# Main.net
KiCad netlist of a schematic drawn in Altium Designer
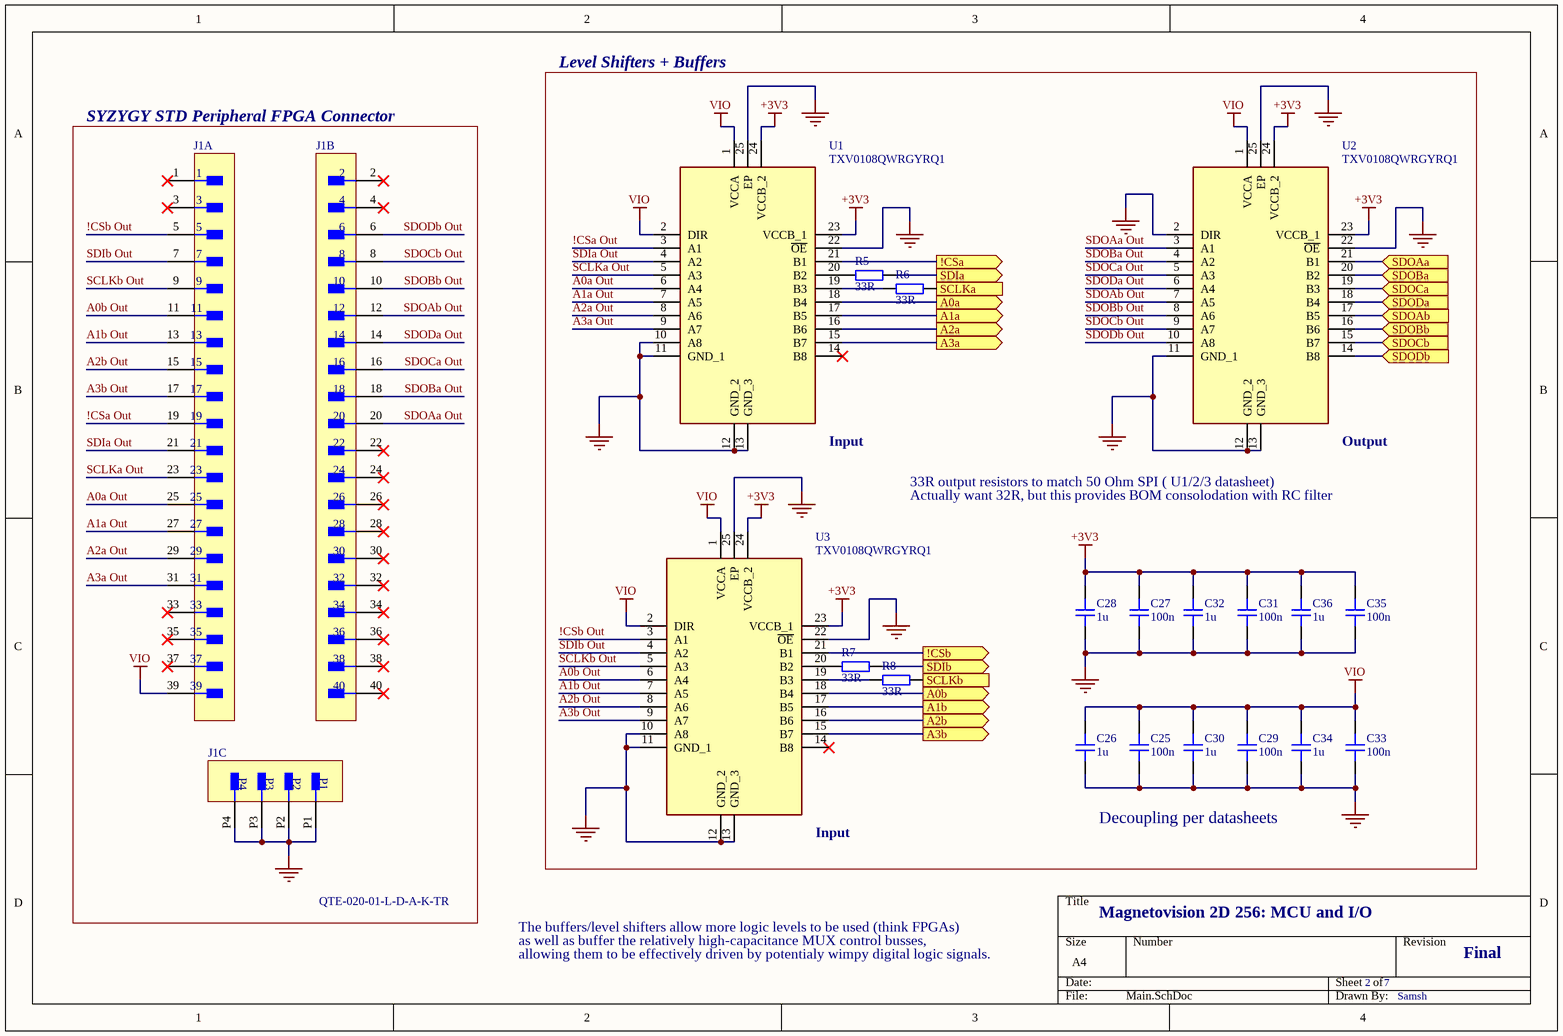
[diagram p0: Main.SchDoc]

(export (version "E")
  (design (tool "Eeschema 10.0.6"))
  (components
    (comp (ref "C25")
      (value "100n")
      (footprint "CAP_0603")
      (description "Capacitor SMD 0603")
      (fields (field (name "SOURCE") "Schematic-Lib-PhilsLab.SchLib"))
      (libsource (lib "Samsh Nanoelectronics") (part "CAP_EL_NP_5MM"))
    )
    (comp (ref "C26")
      (value "1u")
      (footprint "CAP_0603")
      (description "Capacitor SMD 0603")
      (fields (field (name "SOURCE") "Schematic-Lib-PhilsLab.SchLib"))
      (libsource (lib "Samsh Nanoelectronics") (part "CAP_EL_NP_5MM"))
    )
    (comp (ref "C27")
      (value "100n")
      (footprint "CAP_0603")
      (description "Capacitor SMD 0603")
      (fields (field (name "SOURCE") "Schematic-Lib-PhilsLab.SchLib"))
      (libsource (lib "Samsh Nanoelectronics") (part "CAP_EL_NP_5MM"))
    )
    (comp (ref "C28")
      (value "1u")
      (footprint "CAP_0603")
      (description "Capacitor SMD 0603")
      (fields (field (name "SOURCE") "Schematic-Lib-PhilsLab.SchLib"))
      (libsource (lib "Samsh Nanoelectronics") (part "CAP_EL_NP_5MM"))
    )
    (comp (ref "C29")
      (value "100n")
      (footprint "CAP_0603")
      (description "Capacitor SMD 0603")
      (fields (field (name "SOURCE") "Schematic-Lib-PhilsLab.SchLib"))
      (libsource (lib "Samsh Nanoelectronics") (part "CAP_EL_NP_5MM"))
    )
    (comp (ref "C30")
      (value "1u")
      (footprint "CAP_0603")
      (description "Capacitor SMD 0603")
      (fields (field (name "SOURCE") "Schematic-Lib-PhilsLab.SchLib"))
      (libsource (lib "Samsh Nanoelectronics") (part "CAP_EL_NP_5MM"))
    )
    (comp (ref "C31")
      (value "100n")
      (footprint "CAP_0603")
      (description "Capacitor SMD 0603")
      (fields (field (name "SOURCE") "Schematic-Lib-PhilsLab.SchLib"))
      (libsource (lib "Samsh Nanoelectronics") (part "CAP_EL_NP_5MM"))
    )
    (comp (ref "C32")
      (value "1u")
      (footprint "CAP_0603")
      (description "Capacitor SMD 0603")
      (fields (field (name "SOURCE") "Schematic-Lib-PhilsLab.SchLib"))
      (libsource (lib "Samsh Nanoelectronics") (part "CAP_EL_NP_5MM"))
    )
    (comp (ref "C33")
      (value "100n")
      (footprint "CAP_0603")
      (description "Capacitor SMD 0603")
      (fields (field (name "SOURCE") "Schematic-Lib-PhilsLab.SchLib"))
      (libsource (lib "Samsh Nanoelectronics") (part "CAP_EL_NP_5MM"))
    )
    (comp (ref "C34")
      (value "1u")
      (footprint "CAP_0603")
      (description "Capacitor SMD 0603")
      (fields (field (name "SOURCE") "Schematic-Lib-PhilsLab.SchLib"))
      (libsource (lib "Samsh Nanoelectronics") (part "CAP_EL_NP_5MM"))
    )
    (comp (ref "C35")
      (value "100n")
      (footprint "CAP_0603")
      (description "Capacitor SMD 0603")
      (fields (field (name "SOURCE") "Schematic-Lib-PhilsLab.SchLib"))
      (libsource (lib "Samsh Nanoelectronics") (part "CAP_EL_NP_5MM"))
    )
    (comp (ref "C36")
      (value "1u")
      (footprint "CAP_0603")
      (description "Capacitor SMD 0603")
      (fields (field (name "SOURCE") "Schematic-Lib-PhilsLab.SchLib"))
      (libsource (lib "Samsh Nanoelectronics") (part "CAP_EL_NP_5MM"))
    )
    (comp (ref "J1")
      (value "QTE-020-01-L-D-A-K-TR")
      (footprint "FP-QTE-020-01-L-D-A-K-TR_MFG")
      (description "Board to Board & Mezzanine Connectors Q Strip High-Speed Ground Plane Header, 0.80mm Pitch")
      (libsource (lib "") (part "95d99cab9a8bca80e36bdc8dd55fd41_1"))
    )
    (comp (ref "R5")
      (value "33R")
      (footprint "RES_0603")
      (description "Resistor SMD 0603")
      (fields (field (name "SOURCE") "Schematic-Lib-PhilsLab.SchLib"))
      (libsource (lib "Samsh Nanoelectronics") (part "RES_5931"))
    )
    (comp (ref "R6")
      (value "33R")
      (footprint "RES_0603")
      (description "Resistor SMD 0603")
      (fields (field (name "SOURCE") "Schematic-Lib-PhilsLab.SchLib"))
      (libsource (lib "Samsh Nanoelectronics") (part "RES_5931"))
    )
    (comp (ref "R7")
      (value "33R")
      (footprint "RES_0603")
      (description "Resistor SMD 0603")
      (fields (field (name "SOURCE") "Schematic-Lib-PhilsLab.SchLib"))
      (libsource (lib "Samsh Nanoelectronics") (part "RES_5931"))
    )
    (comp (ref "R8")
      (value "33R")
      (footprint "RES_0603")
      (description "Resistor SMD 0603")
      (fields (field (name "SOURCE") "Schematic-Lib-PhilsLab.SchLib"))
      (libsource (lib "Samsh Nanoelectronics") (part "RES_5931"))
    )
    (comp (ref "U1")
      (value "TXV0108QWRGYRQ1")
      (footprint "SamacSys:TXV0108QWRGYRQ1")
      (description "Integrated Circuit")
      (libsource (lib "*") (part "TXV0108QWRGYRQ1"))
    )
    (comp (ref "U2")
      (value "TXV0108QWRGYRQ1")
      (footprint "SamacSys:TXV0108QWRGYRQ1")
      (description "Integrated Circuit")
      (libsource (lib "*") (part "TXV0108QWRGYRQ1"))
    )
    (comp (ref "U3")
      (value "TXV0108QWRGYRQ1")
      (footprint "SamacSys:TXV0108QWRGYRQ1")
      (description "Integrated Circuit")
      (libsource (lib "*") (part "TXV0108QWRGYRQ1"))
    )
  )
  (nets
    (net (code "1") (name "+3V3") (class "Default")
      (node (ref "C27") (pin "2") (pinfunction "2_2") (pintype "passive"))
      (node (ref "C28") (pin "2") (pinfunction "2_2") (pintype "passive"))
      (node (ref "C31") (pin "2") (pinfunction "2_2") (pintype "passive"))
      (node (ref "C32") (pin "2") (pinfunction "2_2") (pintype "passive"))
      (node (ref "C35") (pin "2") (pinfunction "2_2") (pintype "passive"))
      (node (ref "C36") (pin "2") (pinfunction "2_2") (pintype "passive"))
      (node (ref "U1") (pin "23") (pinfunction "VCCB_1_23") (pintype "passive"))
      (node (ref "U1") (pin "24") (pinfunction "VCCB_2_24") (pintype "passive"))
      (node (ref "U2") (pin "23") (pinfunction "VCCB_1_23") (pintype "passive"))
      (node (ref "U2") (pin "24") (pinfunction "VCCB_2_24") (pintype "passive"))
      (node (ref "U3") (pin "23") (pinfunction "VCCB_1_23") (pintype "passive"))
      (node (ref "U3") (pin "24") (pinfunction "VCCB_2_24") (pintype "passive"))
    )
    (net (code "2") (name "/!CSa") (class "Default")
      (node (ref "U1") (pin "21") (pinfunction "B1_21") (pintype "passive"))
    )
    (net (code "3") (name "/!CSa Out") (class "Default")
      (node (ref "J1") (pin "19") (pinfunction "19_19") (pintype "passive"))
      (node (ref "U1") (pin "3") (pinfunction "A1_3") (pintype "passive"))
    )
    (net (code "4") (name "/!CSb") (class "Default")
      (node (ref "U3") (pin "21") (pinfunction "B1_21") (pintype "passive"))
    )
    (net (code "5") (name "/!CSb Out") (class "Default")
      (node (ref "J1") (pin "5") (pinfunction "5_5") (pintype "passive"))
      (node (ref "U3") (pin "3") (pinfunction "A1_3") (pintype "passive"))
    )
    (net (code "6") (name "/A0a") (class "Default")
      (node (ref "U1") (pin "18") (pinfunction "B4_18") (pintype "passive"))
    )
    (net (code "7") (name "/A0a Out") (class "Default")
      (node (ref "J1") (pin "25") (pinfunction "25_25") (pintype "passive"))
      (node (ref "U1") (pin "6") (pinfunction "A4_6") (pintype "passive"))
    )
    (net (code "8") (name "/A0b") (class "Default")
      (node (ref "U3") (pin "18") (pinfunction "B4_18") (pintype "passive"))
    )
    (net (code "9") (name "/A0b Out") (class "Default")
      (node (ref "J1") (pin "11") (pinfunction "11_11") (pintype "passive"))
      (node (ref "U3") (pin "6") (pinfunction "A4_6") (pintype "passive"))
    )
    (net (code "10") (name "/A1a") (class "Default")
      (node (ref "U1") (pin "17") (pinfunction "B5_17") (pintype "passive"))
    )
    (net (code "11") (name "/A1a Out") (class "Default")
      (node (ref "J1") (pin "27") (pinfunction "27_27") (pintype "passive"))
      (node (ref "U1") (pin "7") (pinfunction "A5_7") (pintype "passive"))
    )
    (net (code "12") (name "/A1b") (class "Default")
      (node (ref "U3") (pin "17") (pinfunction "B5_17") (pintype "passive"))
    )
    (net (code "13") (name "/A1b Out") (class "Default")
      (node (ref "J1") (pin "13") (pinfunction "13_13") (pintype "passive"))
      (node (ref "U3") (pin "7") (pinfunction "A5_7") (pintype "passive"))
    )
    (net (code "14") (name "/A2a") (class "Default")
      (node (ref "U1") (pin "16") (pinfunction "B6_16") (pintype "passive"))
    )
    (net (code "15") (name "/A2a Out") (class "Default")
      (node (ref "J1") (pin "29") (pinfunction "29_29") (pintype "passive"))
      (node (ref "U1") (pin "8") (pinfunction "A6_8") (pintype "passive"))
    )
    (net (code "16") (name "/A2b") (class "Default")
      (node (ref "U3") (pin "16") (pinfunction "B6_16") (pintype "passive"))
    )
    (net (code "17") (name "/A2b Out") (class "Default")
      (node (ref "J1") (pin "15") (pinfunction "15_15") (pintype "passive"))
      (node (ref "U3") (pin "8") (pinfunction "A6_8") (pintype "passive"))
    )
    (net (code "18") (name "/A3a") (class "Default")
      (node (ref "U1") (pin "15") (pinfunction "B7_15") (pintype "passive"))
    )
    (net (code "19") (name "/A3a Out") (class "Default")
      (node (ref "J1") (pin "31") (pinfunction "31_31") (pintype "passive"))
      (node (ref "U1") (pin "9") (pinfunction "A7_9") (pintype "passive"))
    )
    (net (code "20") (name "/A3b") (class "Default")
      (node (ref "U3") (pin "15") (pinfunction "B7_15") (pintype "passive"))
    )
    (net (code "21") (name "/A3b Out") (class "Default")
      (node (ref "J1") (pin "17") (pinfunction "17_17") (pintype "passive"))
      (node (ref "U3") (pin "9") (pinfunction "A7_9") (pintype "passive"))
    )
    (net (code "22") (name "/SCLKa") (class "Default")
      (node (ref "R6") (pin "1") (pinfunction "1_1") (pintype "passive"))
    )
    (net (code "23") (name "/SCLKa Out") (class "Default")
      (node (ref "J1") (pin "23") (pinfunction "23_23") (pintype "passive"))
      (node (ref "U1") (pin "5") (pinfunction "A3_5") (pintype "passive"))
    )
    (net (code "24") (name "/SCLKb") (class "Default")
      (node (ref "R8") (pin "1") (pinfunction "1_1") (pintype "passive"))
    )
    (net (code "25") (name "/SCLKb Out") (class "Default")
      (node (ref "J1") (pin "9") (pinfunction "9_9") (pintype "passive"))
      (node (ref "U3") (pin "5") (pinfunction "A3_5") (pintype "passive"))
    )
    (net (code "26") (name "/SDIa") (class "Default")
      (node (ref "R5") (pin "1") (pinfunction "1_1") (pintype "passive"))
    )
    (net (code "27") (name "/SDIa Out") (class "Default")
      (node (ref "J1") (pin "21") (pinfunction "21_21") (pintype "passive"))
      (node (ref "U1") (pin "4") (pinfunction "A2_4") (pintype "passive"))
    )
    (net (code "28") (name "/SDIb") (class "Default")
      (node (ref "R7") (pin "1") (pinfunction "1_1") (pintype "passive"))
    )
    (net (code "29") (name "/SDIb Out") (class "Default")
      (node (ref "J1") (pin "7") (pinfunction "7_7") (pintype "passive"))
      (node (ref "U3") (pin "4") (pinfunction "A2_4") (pintype "passive"))
    )
    (net (code "30") (name "/SDOAa") (class "Default")
      (node (ref "U2") (pin "21") (pinfunction "B1_21") (pintype "passive"))
    )
    (net (code "31") (name "/SDOAa Out") (class "Default")
      (node (ref "J1") (pin "20") (pinfunction "20_20") (pintype "passive"))
      (node (ref "U2") (pin "3") (pinfunction "A1_3") (pintype "passive"))
    )
    (net (code "32") (name "/SDOAb") (class "Default")
      (node (ref "U2") (pin "17") (pinfunction "B5_17") (pintype "passive"))
    )
    (net (code "33") (name "/SDOAb Out") (class "Default")
      (node (ref "J1") (pin "12") (pinfunction "12_12") (pintype "passive"))
      (node (ref "U2") (pin "7") (pinfunction "A5_7") (pintype "passive"))
    )
    (net (code "34") (name "/SDOBa") (class "Default")
      (node (ref "U2") (pin "20") (pinfunction "B2_20") (pintype "passive"))
    )
    (net (code "35") (name "/SDOBa Out") (class "Default")
      (node (ref "J1") (pin "18") (pinfunction "18_18") (pintype "passive"))
      (node (ref "U2") (pin "4") (pinfunction "A2_4") (pintype "passive"))
    )
    (net (code "36") (name "/SDOBb") (class "Default")
      (node (ref "U2") (pin "16") (pinfunction "B6_16") (pintype "passive"))
    )
    (net (code "37") (name "/SDOBb Out") (class "Default")
      (node (ref "J1") (pin "10") (pinfunction "10_10") (pintype "passive"))
      (node (ref "U2") (pin "8") (pinfunction "A6_8") (pintype "passive"))
    )
    (net (code "38") (name "/SDOCa") (class "Default")
      (node (ref "U2") (pin "19") (pinfunction "B3_19") (pintype "passive"))
    )
    (net (code "39") (name "/SDOCa Out") (class "Default")
      (node (ref "J1") (pin "16") (pinfunction "16_16") (pintype "passive"))
      (node (ref "U2") (pin "5") (pinfunction "A3_5") (pintype "passive"))
    )
    (net (code "40") (name "/SDOCb") (class "Default")
      (node (ref "U2") (pin "15") (pinfunction "B7_15") (pintype "passive"))
    )
    (net (code "41") (name "/SDOCb Out") (class "Default")
      (node (ref "J1") (pin "8") (pinfunction "8_8") (pintype "passive"))
      (node (ref "U2") (pin "9") (pinfunction "A7_9") (pintype "passive"))
    )
    (net (code "42") (name "/SDODa") (class "Default")
      (node (ref "U2") (pin "18") (pinfunction "B4_18") (pintype "passive"))
    )
    (net (code "43") (name "/SDODa Out") (class "Default")
      (node (ref "J1") (pin "14") (pinfunction "14_14") (pintype "passive"))
      (node (ref "U2") (pin "6") (pinfunction "A4_6") (pintype "passive"))
    )
    (net (code "44") (name "/SDODb") (class "Default")
      (node (ref "U2") (pin "14") (pinfunction "B8_14") (pintype "passive"))
    )
    (net (code "45") (name "/SDODb Out") (class "Default")
      (node (ref "J1") (pin "6") (pinfunction "6_6") (pintype "passive"))
      (node (ref "U2") (pin "10") (pinfunction "A8_10") (pintype "passive"))
    )
    (net (code "46") (name "GND") (class "Default")
      (node (ref "C25") (pin "1") (pinfunction "1_1") (pintype "passive"))
      (node (ref "C26") (pin "1") (pinfunction "1_1") (pintype "passive"))
      (node (ref "C27") (pin "1") (pinfunction "1_1") (pintype "passive"))
      (node (ref "C28") (pin "1") (pinfunction "1_1") (pintype "passive"))
      (node (ref "C29") (pin "1") (pinfunction "1_1") (pintype "passive"))
      (node (ref "C30") (pin "1") (pinfunction "1_1") (pintype "passive"))
      (node (ref "C31") (pin "1") (pinfunction "1_1") (pintype "passive"))
      (node (ref "C32") (pin "1") (pinfunction "1_1") (pintype "passive"))
      (node (ref "C33") (pin "1") (pinfunction "1_1") (pintype "passive"))
      (node (ref "C34") (pin "1") (pinfunction "1_1") (pintype "passive"))
      (node (ref "C35") (pin "1") (pinfunction "1_1") (pintype "passive"))
      (node (ref "C36") (pin "1") (pinfunction "1_1") (pintype "passive"))
      (node (ref "J1") (pin "P1") (pinfunction "P1_P1") (pintype "passive"))
      (node (ref "J1") (pin "P2") (pinfunction "P2_P2") (pintype "passive"))
      (node (ref "J1") (pin "P3") (pinfunction "P3_P3") (pintype "passive"))
      (node (ref "J1") (pin "P4") (pinfunction "P4_P4") (pintype "passive"))
      (node (ref "U1") (pin "10") (pinfunction "A8_10") (pintype "passive"))
      (node (ref "U1") (pin "11") (pinfunction "GND_1_11") (pintype "passive"))
      (node (ref "U1") (pin "12") (pinfunction "GND_2_12") (pintype "passive"))
      (node (ref "U1") (pin "13") (pinfunction "GND_3_13") (pintype "passive"))
      (node (ref "U1") (pin "22") (pinfunction "~{OE}_22") (pintype "passive"))
      (node (ref "U1") (pin "25") (pinfunction "EP_25") (pintype "passive"))
      (node (ref "U2") (pin "11") (pinfunction "GND_1_11") (pintype "passive"))
      (node (ref "U2") (pin "12") (pinfunction "GND_2_12") (pintype "passive"))
      (node (ref "U2") (pin "13") (pinfunction "GND_3_13") (pintype "passive"))
      (node (ref "U2") (pin "2") (pinfunction "DIR_2") (pintype "passive"))
      (node (ref "U2") (pin "22") (pinfunction "~{OE}_22") (pintype "passive"))
      (node (ref "U2") (pin "25") (pinfunction "EP_25") (pintype "passive"))
      (node (ref "U3") (pin "10") (pinfunction "A8_10") (pintype "passive"))
      (node (ref "U3") (pin "11") (pinfunction "GND_1_11") (pintype "passive"))
      (node (ref "U3") (pin "12") (pinfunction "GND_2_12") (pintype "passive"))
      (node (ref "U3") (pin "13") (pinfunction "GND_3_13") (pintype "passive"))
      (node (ref "U3") (pin "22") (pinfunction "~{OE}_22") (pintype "passive"))
      (node (ref "U3") (pin "25") (pinfunction "EP_25") (pintype "passive"))
    )
    (net (code "47") (name "Net-(U1-B2)") (class "Default")
      (node (ref "R5") (pin "2") (pinfunction "2_2") (pintype "passive"))
      (node (ref "U1") (pin "20") (pinfunction "B2_20") (pintype "passive"))
    )
    (net (code "48") (name "Net-(U1-B3)") (class "Default")
      (node (ref "R6") (pin "2") (pinfunction "2_2") (pintype "passive"))
      (node (ref "U1") (pin "19") (pinfunction "B3_19") (pintype "passive"))
    )
    (net (code "49") (name "Net-(U3-B2)") (class "Default")
      (node (ref "R7") (pin "2") (pinfunction "2_2") (pintype "passive"))
      (node (ref "U3") (pin "20") (pinfunction "B2_20") (pintype "passive"))
    )
    (net (code "50") (name "Net-(U3-B3)") (class "Default")
      (node (ref "R8") (pin "2") (pinfunction "2_2") (pintype "passive"))
      (node (ref "U3") (pin "19") (pinfunction "B3_19") (pintype "passive"))
    )
    (net (code "51") (name "VIO") (class "Default")
      (node (ref "C25") (pin "2") (pinfunction "2_2") (pintype "passive"))
      (node (ref "C26") (pin "2") (pinfunction "2_2") (pintype "passive"))
      (node (ref "C29") (pin "2") (pinfunction "2_2") (pintype "passive"))
      (node (ref "C30") (pin "2") (pinfunction "2_2") (pintype "passive"))
      (node (ref "C33") (pin "2") (pinfunction "2_2") (pintype "passive"))
      (node (ref "C34") (pin "2") (pinfunction "2_2") (pintype "passive"))
      (node (ref "J1") (pin "39") (pinfunction "39_39") (pintype "passive"))
      (node (ref "U1") (pin "1") (pinfunction "VCCA_1") (pintype "passive"))
      (node (ref "U1") (pin "2") (pinfunction "DIR_2") (pintype "passive"))
      (node (ref "U2") (pin "1") (pinfunction "VCCA_1") (pintype "passive"))
      (node (ref "U3") (pin "1") (pinfunction "VCCA_1") (pintype "passive"))
      (node (ref "U3") (pin "2") (pinfunction "DIR_2") (pintype "passive"))
    )
    (net (code "52") (name "unconnected-(J1-Pad1)") (class "Default")
      (node (ref "J1") (pin "1") (pinfunction "1_1") (pintype "passive+no_connect"))
    )
    (net (code "53") (name "unconnected-(J1-Pad2)") (class "Default")
      (node (ref "J1") (pin "2") (pinfunction "2_2") (pintype "passive+no_connect"))
    )
    (net (code "54") (name "unconnected-(J1-Pad3)") (class "Default")
      (node (ref "J1") (pin "3") (pinfunction "3_3") (pintype "passive+no_connect"))
    )
    (net (code "55") (name "unconnected-(J1-Pad4)") (class "Default")
      (node (ref "J1") (pin "4") (pinfunction "4_4") (pintype "passive+no_connect"))
    )
    (net (code "56") (name "unconnected-(J1-Pad22)") (class "Default")
      (node (ref "J1") (pin "22") (pinfunction "22_22") (pintype "passive+no_connect"))
    )
    (net (code "57") (name "unconnected-(J1-Pad24)") (class "Default")
      (node (ref "J1") (pin "24") (pinfunction "24_24") (pintype "passive+no_connect"))
    )
    (net (code "58") (name "unconnected-(J1-Pad26)") (class "Default")
      (node (ref "J1") (pin "26") (pinfunction "26_26") (pintype "passive+no_connect"))
    )
    (net (code "59") (name "unconnected-(J1-Pad28)") (class "Default")
      (node (ref "J1") (pin "28") (pinfunction "28_28") (pintype "passive+no_connect"))
    )
    (net (code "60") (name "unconnected-(J1-Pad30)") (class "Default")
      (node (ref "J1") (pin "30") (pinfunction "30_30") (pintype "passive+no_connect"))
    )
    (net (code "61") (name "unconnected-(J1-Pad32)") (class "Default")
      (node (ref "J1") (pin "32") (pinfunction "32_32") (pintype "passive+no_connect"))
    )
    (net (code "62") (name "unconnected-(J1-Pad33)") (class "Default")
      (node (ref "J1") (pin "33") (pinfunction "33_33") (pintype "passive+no_connect"))
    )
    (net (code "63") (name "unconnected-(J1-Pad34)") (class "Default")
      (node (ref "J1") (pin "34") (pinfunction "34_34") (pintype "passive+no_connect"))
    )
    (net (code "64") (name "unconnected-(J1-Pad35)") (class "Default")
      (node (ref "J1") (pin "35") (pinfunction "35_35") (pintype "passive+no_connect"))
    )
    (net (code "65") (name "unconnected-(J1-Pad36)") (class "Default")
      (node (ref "J1") (pin "36") (pinfunction "36_36") (pintype "passive+no_connect"))
    )
    (net (code "66") (name "unconnected-(J1-Pad37)") (class "Default")
      (node (ref "J1") (pin "37") (pinfunction "37_37") (pintype "passive+no_connect"))
    )
    (net (code "67") (name "unconnected-(J1-Pad38)") (class "Default")
      (node (ref "J1") (pin "38") (pinfunction "38_38") (pintype "passive+no_connect"))
    )
    (net (code "68") (name "unconnected-(J1-Pad40)") (class "Default")
      (node (ref "J1") (pin "40") (pinfunction "40_40") (pintype "passive+no_connect"))
    )
    (net (code "69") (name "unconnected-(U1-B8-Pad14)") (class "Default")
      (node (ref "U1") (pin "14") (pinfunction "B8_14") (pintype "passive+no_connect"))
    )
    (net (code "70") (name "unconnected-(U3-B8-Pad14)") (class "Default")
      (node (ref "U3") (pin "14") (pinfunction "B8_14") (pintype "passive+no_connect"))
    )
  )
)
